# Mussel_heartrate_RevC.net
KiCad netlist of a schematic drawn in EAGLE
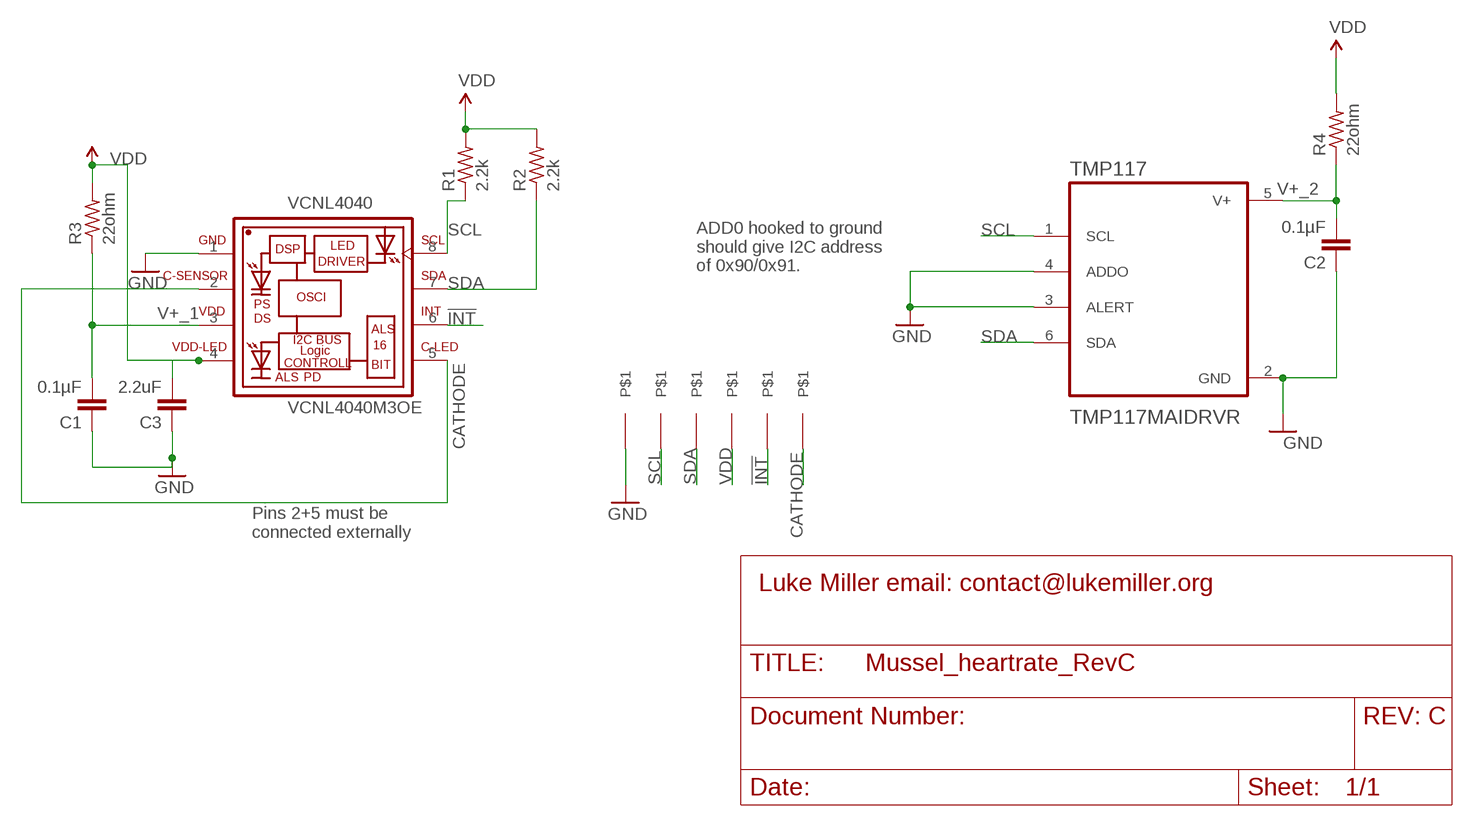
[diagram p0: schematic, sheet 1]

(export (version "E")
  (design (tool "Eeschema 10.0.6"))
  (components
    (comp (ref "!INT")
      (value "PINHD-1X10.7MM_DRILL")
      (footprint "eagle-import:1X01_SMALL_0.7")
      (libsource (lib "eagle-import") (part "PINHD-1X10.7MM_DRILL"))
    )
    (comp (ref "!INT1")
      (value "PINHD-1X10.7MM_DRILL")
      (footprint "eagle-import:1X01_SMALL_0.7")
      (libsource (lib "eagle-import") (part "PINHD-1X10.7MM_DRILL"))
    )
    (comp (ref "C1")
      (value "0.1µF")
      (footprint "eagle-import:C0402")
      (libsource (lib "eagle-import") (part "CAP0402"))
    )
    (comp (ref "C2")
      (value "0.1µF")
      (footprint "eagle-import:C0402")
      (libsource (lib "eagle-import") (part "CAP0402"))
    )
    (comp (ref "C3")
      (value "2.2uF")
      (footprint "eagle-import:C0402")
      (libsource (lib "eagle-import") (part "CAP0402"))
    )
    (comp (ref "GND")
      (value "PINHD-1X1SMALL")
      (footprint "eagle-import:1X01_SMALL")
      (libsource (lib "eagle-import") (part "PINHD-1X1SMALL"))
    )
    (comp (ref "R1")
      (value "2.2k")
      (footprint "eagle-import:R0402")
      (libsource (lib "eagle-import") (part "RESISTOR_SMDR0402"))
    )
    (comp (ref "R2")
      (value "2.2k")
      (footprint "eagle-import:R0402")
      (libsource (lib "eagle-import") (part "RESISTOR_SMDR0402"))
    )
    (comp (ref "R3")
      (value "22ohm")
      (footprint "eagle-import:R0402")
      (libsource (lib "eagle-import") (part "RESISTOR_SMDR0402"))
    )
    (comp (ref "R4")
      (value "22ohm")
      (footprint "eagle-import:R0402")
      (libsource (lib "eagle-import") (part "RESISTOR_SMDR0402"))
    )
    (comp (ref "SCL")
      (value "PINHD-1X1SMALL")
      (footprint "eagle-import:1X01_SMALL")
      (libsource (lib "eagle-import") (part "PINHD-1X1SMALL"))
    )
    (comp (ref "SDA")
      (value "PINHD-1X1SMALL")
      (footprint "eagle-import:1X01_SMALL")
      (libsource (lib "eagle-import") (part "PINHD-1X1SMALL"))
    )
    (comp (ref "TMP117")
      (value "TMP117MAIDRVR")
      (footprint "eagle-import:SON65P200X200X80-7N")
      (fields (field (name "MF") "Texas Instruments"))
      (libsource (lib "eagle-import") (part "TMP117MAIDRVR"))
    )
    (comp (ref "VCNL4040")
      (value "VCNL4040M3OE")
      (footprint "eagle-import:VISHAY_VCNL4040_4X2X1.1")
      (fields (field (name "MF") "Vishay"))
      (libsource (lib "eagle-import") (part "VCNL4040M3OE"))
    )
    (comp (ref "VDD")
      (value "PINHD-1X1SMALL")
      (footprint "eagle-import:1X01_SMALL")
      (libsource (lib "eagle-import") (part "PINHD-1X1SMALL"))
    )
  )
  (nets
    (net (code "1") (name "/CATHODE") (class "Default")
      (node (ref "!INT1") (pin "P$1") (pinfunction "P$1_P$1") (pintype "bidirectional"))
      (node (ref "VCNL4040") (pin "2") (pinfunction "C-SENSOR_2") (pintype "output"))
      (node (ref "VCNL4040") (pin "5") (pinfunction "C-LED_5") (pintype "output"))
    )
    (net (code "2") (name "/SCL") (class "Default")
      (node (ref "R1") (pin "1") (pinfunction "1_1") (pintype "passive"))
      (node (ref "SCL") (pin "1") (pinfunction "P$1_1") (pintype "bidirectional"))
      (node (ref "TMP117") (pin "1") (pinfunction "SCL_1") (pintype "input"))
      (node (ref "VCNL4040") (pin "8") (pinfunction "SCL_8") (pintype "input"))
    )
    (net (code "3") (name "/SDA") (class "Default")
      (node (ref "R2") (pin "1") (pinfunction "1_1") (pintype "passive"))
      (node (ref "SDA") (pin "1") (pinfunction "P$1_1") (pintype "bidirectional"))
      (node (ref "TMP117") (pin "6") (pinfunction "SDA_6") (pintype "bidirectional"))
      (node (ref "VCNL4040") (pin "7") (pinfunction "SDA_7") (pintype "bidirectional"))
    )
    (net (code "4") (name "/V+_1") (class "Default")
      (node (ref "C1") (pin "2") (pinfunction "2_2") (pintype "passive"))
      (node (ref "R3") (pin "1") (pinfunction "1_1") (pintype "passive"))
      (node (ref "VCNL4040") (pin "3") (pinfunction "VDD_3") (pintype "power_in"))
    )
    (net (code "5") (name "/V+_2") (class "Default")
      (node (ref "C2") (pin "2") (pinfunction "2_2") (pintype "passive"))
      (node (ref "R4") (pin "1") (pinfunction "1_1") (pintype "passive"))
      (node (ref "TMP117") (pin "5") (pinfunction "V+_5") (pintype "power_in"))
    )
    (net (code "6") (name "/~{INT}") (class "Default")
      (node (ref "!INT") (pin "P$1") (pinfunction "P$1_P$1") (pintype "bidirectional"))
      (node (ref "VCNL4040") (pin "6") (pinfunction "INT_6") (pintype "output"))
    )
    (net (code "7") (name "GND") (class "Default")
      (node (ref "C1") (pin "1") (pinfunction "1_1") (pintype "passive"))
      (node (ref "C2") (pin "1") (pinfunction "1_1") (pintype "passive"))
      (node (ref "C3") (pin "1") (pinfunction "1_1") (pintype "passive"))
      (node (ref "GND") (pin "1") (pinfunction "P$1_1") (pintype "bidirectional"))
      (node (ref "TMP117") (pin "2") (pinfunction "GND_2") (pintype "power_in"))
      (node (ref "TMP117") (pin "3") (pinfunction "ALERT_3") (pintype "bidirectional"))
      (node (ref "TMP117") (pin "4") (pinfunction "ADDO_4") (pintype "bidirectional"))
      (node (ref "VCNL4040") (pin "1") (pinfunction "GND_1") (pintype "power_in"))
    )
    (net (code "8") (name "VCC") (class "Default")
      (node (ref "C3") (pin "2") (pinfunction "2_2") (pintype "passive"))
      (node (ref "R1") (pin "2") (pinfunction "2_2") (pintype "passive"))
      (node (ref "R2") (pin "2") (pinfunction "2_2") (pintype "passive"))
      (node (ref "R3") (pin "2") (pinfunction "2_2") (pintype "passive"))
      (node (ref "R4") (pin "2") (pinfunction "2_2") (pintype "passive"))
      (node (ref "VCNL4040") (pin "4") (pinfunction "VDD-LED_4") (pintype "power_in"))
      (node (ref "VDD") (pin "1") (pinfunction "P$1_1") (pintype "bidirectional"))
    )
  )
)
